# Power.net
KiCad netlist of a schematic drawn in Altium Designer
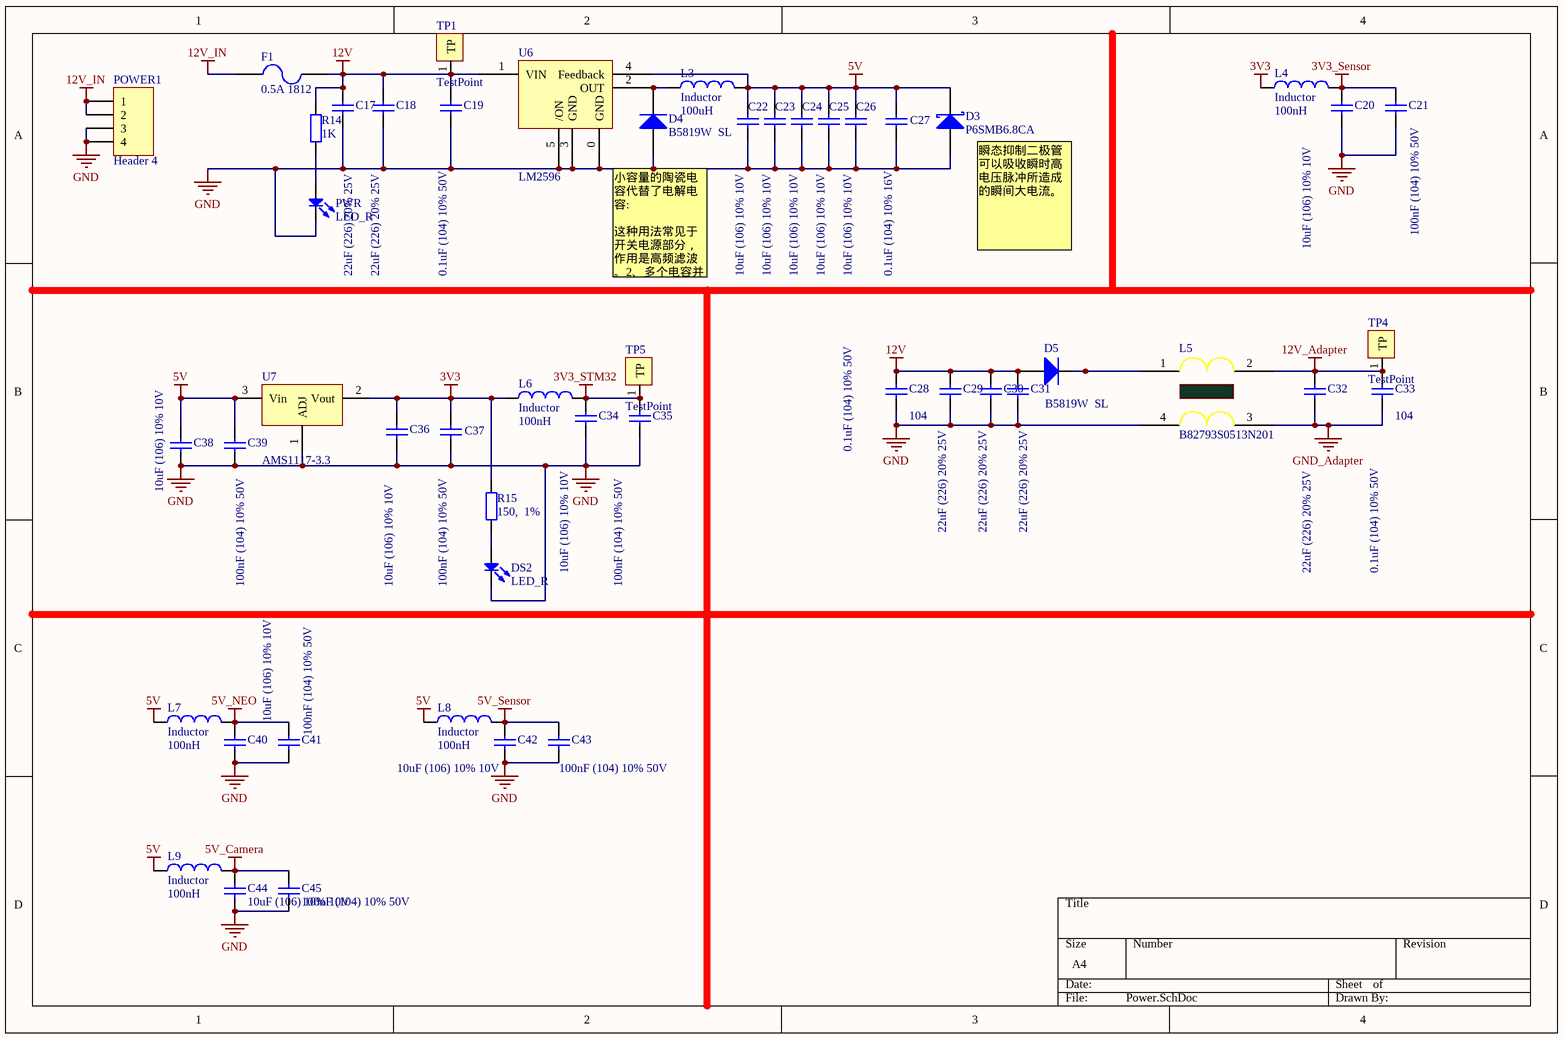
[diagram p0: Power.SchDoc]

(export (version "E")
  (design (tool "Eeschema 10.0.6"))
  (components
    (comp (ref "C17")
      (value "22uF (226) 20% 25V")
      (footprint "0805_C")
      (description "贴片电容")
      (libsource (lib "Miscellaneous Devices LC") (part "0805 22uF (226) 20% 25V"))
    )
    (comp (ref "C18")
      (value "22uF (226) 20% 25V")
      (footprint "0805_C")
      (description "贴片电容")
      (libsource (lib "Miscellaneous Devices LC") (part "0805 22uF (226) 20% 25V"))
    )
    (comp (ref "C19")
      (value "0.1uF (104) 10% 50V")
      (footprint "0805_C")
      (description "Capacitor")
      (fields (field (name "PUBLISHER") "Altium Limited"))
      (libsource (lib "Miscellaneous Devices") (part "Cap"))
    )
    (comp (ref "C20")
      (value "10uF (106) 10% 10V")
      (footprint "0603_C")
      (description "贴片电容")
      (libsource (lib "Miscellaneous Devices LC") (part "0603 10uF (106) 10% 10V"))
    )
    (comp (ref "C21")
      (value "100nF (104) 10% 50V")
      (footprint "0603_C")
      (description "贴片电容")
      (libsource (lib "Miscellaneous Devices LC") (part "0603 100nF (104) 10% 50V"))
    )
    (comp (ref "C22")
      (value "10uF (106) 10% 10V")
      (footprint "0603_C")
      (description "贴片电容")
      (libsource (lib "Miscellaneous Devices LC") (part "0603 10uF (106) 10% 10V"))
    )
    (comp (ref "C23")
      (value "10uF (106) 10% 10V")
      (footprint "0603_C")
      (description "贴片电容")
      (libsource (lib "Miscellaneous Devices LC") (part "0603 10uF (106) 10% 10V"))
    )
    (comp (ref "C24")
      (value "10uF (106) 10% 10V")
      (footprint "0603_C")
      (description "贴片电容")
      (libsource (lib "Miscellaneous Devices LC") (part "0603 10uF (106) 10% 10V"))
    )
    (comp (ref "C25")
      (value "10uF (106) 10% 10V")
      (footprint "0603_C")
      (description "贴片电容")
      (libsource (lib "Miscellaneous Devices LC") (part "0603 10uF (106) 10% 10V"))
    )
    (comp (ref "C26")
      (value "10uF (106) 10% 10V")
      (footprint "0603_C")
      (description "贴片电容")
      (libsource (lib "Miscellaneous Devices LC") (part "0603 10uF (106) 10% 10V"))
    )
    (comp (ref "C27")
      (value "0.1uF (104) 10% 16V")
      (footprint "0603_C")
      (description "Capacitor")
      (fields (field (name "PUBLISHER") "Altium Limited"))
      (libsource (lib "Miscellaneous Devices") (part "Cap"))
    )
    (comp (ref "C28")
      (value "0.1uF (104) 10% 50V")
      (footprint "0805_C")
      (description "Capacitor")
      (fields (field (name "ALTIUM_VALUE") "104") (field (name "PUBLISHER") "Altium Limited"))
      (libsource (lib "Miscellaneous Devices") (part "Cap"))
    )
    (comp (ref "C29")
      (value "22uF (226) 20% 25V")
      (footprint "0805_C")
      (description "贴片电容")
      (libsource (lib "Miscellaneous Devices LC") (part "0805 22uF (226) 20% 25V"))
    )
    (comp (ref "C30")
      (value "22uF (226) 20% 25V")
      (footprint "0805_C")
      (description "贴片电容")
      (libsource (lib "Miscellaneous Devices LC") (part "0805 22uF (226) 20% 25V"))
    )
    (comp (ref "C31")
      (value "22uF (226) 20% 25V")
      (footprint "0805_C")
      (description "贴片电容")
      (libsource (lib "Miscellaneous Devices LC") (part "0805 22uF (226) 20% 25V"))
    )
    (comp (ref "C32")
      (value "22uF (226) 20% 25V")
      (footprint "0805_C")
      (description "贴片电容")
      (libsource (lib "Miscellaneous Devices LC") (part "0805 22uF (226) 20% 25V"))
    )
    (comp (ref "C33")
      (value "0.1uF (104) 10% 50V")
      (footprint "0805_C")
      (description "Capacitor")
      (fields (field (name "ALTIUM_VALUE") "104") (field (name "PUBLISHER") "Altium Limited"))
      (libsource (lib "Miscellaneous Devices") (part "Cap"))
    )
    (comp (ref "C34")
      (value "10uF (106) 10% 10V")
      (footprint "0603_C")
      (description "贴片电容")
      (libsource (lib "Miscellaneous Devices LC") (part "0603 10uF (106) 10% 10V"))
    )
    (comp (ref "C35")
      (value "100nF (104) 10% 50V")
      (footprint "0603_C")
      (description "贴片电容")
      (libsource (lib "Miscellaneous Devices LC") (part "0603 100nF (104) 10% 50V"))
    )
    (comp (ref "C36")
      (value "10uF (106) 10% 10V")
      (footprint "0603_C")
      (description "贴片电容")
      (libsource (lib "Miscellaneous Devices LC") (part "0603 10uF (106) 10% 10V"))
    )
    (comp (ref "C37")
      (value "100nF (104) 10% 50V")
      (footprint "0603_C")
      (description "贴片电容")
      (libsource (lib "Miscellaneous Devices LC") (part "0603 100nF (104) 10% 50V"))
    )
    (comp (ref "C38")
      (value "10uF (106) 10% 10V")
      (footprint "0603_C")
      (description "贴片电容")
      (libsource (lib "Miscellaneous Devices LC") (part "0603 10uF (106) 10% 10V"))
    )
    (comp (ref "C39")
      (value "100nF (104) 10% 50V")
      (footprint "0603_C")
      (description "贴片电容")
      (libsource (lib "Miscellaneous Devices LC") (part "0603 100nF (104) 10% 50V"))
    )
    (comp (ref "C40")
      (value "10uF (106) 10% 10V")
      (footprint "0603_C")
      (description "贴片电容")
      (libsource (lib "Miscellaneous Devices LC") (part "0603 10uF (106) 10% 10V"))
    )
    (comp (ref "C41")
      (value "100nF (104) 10% 50V")
      (footprint "0603_C")
      (description "贴片电容")
      (libsource (lib "Miscellaneous Devices LC") (part "0603 100nF (104) 10% 50V"))
    )
    (comp (ref "C42")
      (value "10uF (106) 10% 10V")
      (footprint "0603_C")
      (description "贴片电容")
      (libsource (lib "Miscellaneous Devices LC") (part "0603 10uF (106) 10% 10V"))
    )
    (comp (ref "C43")
      (value "100nF (104) 10% 50V")
      (footprint "0603_C")
      (description "贴片电容")
      (libsource (lib "Miscellaneous Devices LC") (part "0603 100nF (104) 10% 50V"))
    )
    (comp (ref "C44")
      (value "10uF (106) 10% 10V")
      (footprint "0603_C")
      (description "贴片电容")
      (libsource (lib "Miscellaneous Devices LC") (part "0603 10uF (106) 10% 10V"))
    )
    (comp (ref "C45")
      (value "100nF (104) 10% 50V")
      (footprint "0603_C")
      (description "贴片电容")
      (libsource (lib "Miscellaneous Devices LC") (part "0603 100nF (104) 10% 50V"))
    )
    (comp (ref "D3")
      (value "P6SMB6.8CA")
      (footprint "SMB(DO-214AA)_S1")
      (description "Schottky Diode")
      (fields (field (name "PUBLISHER") "Altium Limited"))
      (libsource (lib "Miscellaneous Devices") (part "D Schottky"))
    )
    (comp (ref "D4")
      (value "B5819W  SL")
      (footprint "SOD-123")
      (description "肖特基二极管")
      (libsource (lib "Miscellaneous Devices LC") (part "SOD-123 B5819W  SL"))
    )
    (comp (ref "D5")
      (value "B5819W  SL")
      (footprint "SOD-123")
      (description "肖特基二极管")
      (libsource (lib "Miscellaneous Devices LC") (part "SOD-123 B5819W  SL"))
    )
    (comp (ref "DS2")
      (value "LED_R")
      (footprint "LED0603")
      (description "Typical RED, GREEN, YELLOW, AMBER GaAs LED")
      (fields (field (name "PUBLISHER") "Altium Limited"))
      (libsource (lib "Devices") (part "LED"))
    )
    (comp (ref "F1")
      (value "0.5A 1812")
      (footprint "1812")
      (description "Fuse")
      (fields (field (name "PUBLISHER") "Altium Limited"))
      (libsource (lib "Miscellaneous Devices") (part "Fuse 2"))
    )
    (comp (ref "L3")
      (value "Inductor")
      (footprint "L1050(10x10x4)")
      (fields (field (name "ALTIUM_VALUE") "100uH") (field (name "PUBLISHER") "Altium Limited"))
      (libsource (lib "Miscellaneous Devices") (part "Inductor"))
    )
    (comp (ref "L4")
      (value "Inductor")
      (footprint "0603_L")
      (fields (field (name "ALTIUM_VALUE") "100nH") (field (name "PUBLISHER") "Altium Limited"))
      (libsource (lib "Miscellaneous Devices") (part "Inductor"))
    )
    (comp (ref "L5")
      (value "B82793S0513N201")
      (footprint "B82793S0513N201_Yes")
      (libsource (lib "滤波器") (part "B82793S0513N201"))
    )
    (comp (ref "L6")
      (value "Inductor")
      (footprint "0603_L")
      (fields (field (name "ALTIUM_VALUE") "100nH") (field (name "PUBLISHER") "Altium Limited"))
      (libsource (lib "Miscellaneous Devices") (part "Inductor"))
    )
    (comp (ref "L7")
      (value "Inductor")
      (footprint "0603_L")
      (fields (field (name "ALTIUM_VALUE") "100nH") (field (name "PUBLISHER") "Altium Limited"))
      (libsource (lib "Miscellaneous Devices") (part "Inductor"))
    )
    (comp (ref "L8")
      (value "Inductor")
      (footprint "0603_L")
      (fields (field (name "ALTIUM_VALUE") "100nH") (field (name "PUBLISHER") "Altium Limited"))
      (libsource (lib "Miscellaneous Devices") (part "Inductor"))
    )
    (comp (ref "L9")
      (value "Inductor")
      (footprint "0603_L")
      (fields (field (name "ALTIUM_VALUE") "100nH") (field (name "PUBLISHER") "Altium Limited"))
      (libsource (lib "Miscellaneous Devices") (part "Inductor"))
    )
    (comp (ref "POWER1")
      (value "Header 4")
      (footprint "XH2.54_4P")
      (description "Header, 4-Pin")
      (fields (field (name "PUBLISHER") "Altium Limited"))
      (libsource (lib "Miscellaneous Connectors") (part "Header 4"))
    )
    (comp (ref "PWR")
      (value "LED_R")
      (footprint "LED0603")
      (description "Typical RED, GREEN, YELLOW, AMBER GaAs LED")
      (fields (field (name "PUBLISHER") "Altium Limited"))
      (libsource (lib "Devices") (part "LED"))
    )
    (comp (ref "R14")
      (value "1K")
      (footprint "R0603")
      (description "Resistor")
      (fields (field (name "PUBLISHER") "Altium Limited"))
      (libsource (lib "STM32F103C8T6(原理图库)") (part "Res2"))
    )
    (comp (ref "R15")
      (value "150,  1%")
      (footprint "R0603")
      (description "Resistor")
      (fields (field (name "PUBLISHER") "Altium Limited"))
      (libsource (lib "STM32F103C8T6(原理图库)") (part "Res2"))
    )
    (comp (ref "TP1") (value "TestPoint") (footprint "TP") (libsource (lib "my lib1") (part "TP")))
    (comp (ref "TP4") (value "TestPoint") (footprint "TP") (libsource (lib "my lib1") (part "TP")))
    (comp (ref "TP5") (value "TestPoint") (footprint "TP") (libsource (lib "my lib1") (part "TP")))
    (comp (ref "U6") (value "LM2596") (libsource (lib "STM32F103C8T6(原理图库)") (part "LM2576")))
    (comp (ref "U7")
      (value "AMS1117-3.3")
      (footprint "SOT-223")
      (description "3-Terminal Adjustable Positive Voltage Regulator")
      (libsource (lib "稳压器件") (part "LM317"))
    )
  )
  (nets
    (net (code "1") (name "3V3") (class "Default")
      (node (ref "C36") (pin "2") (pinfunction "2_2") (pintype "passive"))
      (node (ref "C37") (pin "2") (pinfunction "2_2") (pintype "passive"))
      (node (ref "L4") (pin "1") (pinfunction "1_1") (pintype "passive"))
      (node (ref "L6") (pin "1") (pinfunction "1_1") (pintype "passive"))
      (node (ref "R15") (pin "1") (pinfunction "1_1") (pintype "passive"))
      (node (ref "U7") (pin "2") (pinfunction "Vout_2") (pintype "passive"))
    )
    (net (code "2") (name "3V3_STM32") (class "Default")
      (node (ref "C34") (pin "2") (pinfunction "2_2") (pintype "passive"))
      (node (ref "C35") (pin "2") (pinfunction "2_2") (pintype "passive"))
      (node (ref "L6") (pin "2") (pinfunction "2_2") (pintype "passive"))
      (node (ref "TP5") (pin "1") (pinfunction "TP_1") (pintype "passive"))
    )
    (net (code "3") (name "3V3_Sensor") (class "Default")
      (node (ref "C20") (pin "2") (pinfunction "2_2") (pintype "passive"))
      (node (ref "C21") (pin "2") (pinfunction "2_2") (pintype "passive"))
      (node (ref "L4") (pin "2") (pinfunction "2_2") (pintype "passive"))
    )
    (net (code "4") (name "5V") (class "Default")
      (node (ref "C22") (pin "2") (pinfunction "2_2") (pintype "passive"))
      (node (ref "C23") (pin "2") (pinfunction "2_2") (pintype "passive"))
      (node (ref "C24") (pin "2") (pinfunction "2_2") (pintype "passive"))
      (node (ref "C25") (pin "2") (pinfunction "2_2") (pintype "passive"))
      (node (ref "C26") (pin "2") (pinfunction "2_2") (pintype "passive"))
      (node (ref "C27") (pin "2") (pinfunction "2_2") (pintype "passive"))
      (node (ref "C38") (pin "2") (pinfunction "2_2") (pintype "passive"))
      (node (ref "C39") (pin "2") (pinfunction "2_2") (pintype "passive"))
      (node (ref "D3") (pin "2") (pinfunction "K_2") (pintype "passive"))
      (node (ref "L3") (pin "2") (pinfunction "2_2") (pintype "passive"))
      (node (ref "L7") (pin "1") (pinfunction "1_1") (pintype "passive"))
      (node (ref "L8") (pin "1") (pinfunction "1_1") (pintype "passive"))
      (node (ref "L9") (pin "1") (pinfunction "1_1") (pintype "passive"))
      (node (ref "U6") (pin "4") (pinfunction "Feedback_4") (pintype "passive"))
      (node (ref "U7") (pin "3") (pinfunction "Vin_3") (pintype "passive"))
    )
    (net (code "5") (name "5V_Camera") (class "Default")
      (node (ref "C44") (pin "2") (pinfunction "2_2") (pintype "passive"))
      (node (ref "C45") (pin "2") (pinfunction "2_2") (pintype "passive"))
      (node (ref "L9") (pin "2") (pinfunction "2_2") (pintype "passive"))
    )
    (net (code "6") (name "5V_NEO") (class "Default")
      (node (ref "C40") (pin "2") (pinfunction "2_2") (pintype "passive"))
      (node (ref "C41") (pin "2") (pinfunction "2_2") (pintype "passive"))
      (node (ref "L7") (pin "2") (pinfunction "2_2") (pintype "passive"))
    )
    (net (code "7") (name "5V_Sensor") (class "Default")
      (node (ref "C42") (pin "2") (pinfunction "2_2") (pintype "passive"))
      (node (ref "C43") (pin "2") (pinfunction "2_2") (pintype "passive"))
      (node (ref "L8") (pin "2") (pinfunction "2_2") (pintype "passive"))
    )
    (net (code "8") (name "12V") (class "Default")
      (node (ref "C17") (pin "2") (pinfunction "2_2") (pintype "passive"))
      (node (ref "C18") (pin "2") (pinfunction "2_2") (pintype "passive"))
      (node (ref "C19") (pin "2") (pinfunction "2_2") (pintype "passive"))
      (node (ref "C28") (pin "2") (pinfunction "2_2") (pintype "passive"))
      (node (ref "C29") (pin "2") (pinfunction "2_2") (pintype "passive"))
      (node (ref "C30") (pin "2") (pinfunction "2_2") (pintype "passive"))
      (node (ref "C31") (pin "2") (pinfunction "2_2") (pintype "passive"))
      (node (ref "D5") (pin "1") (pinfunction "A_1") (pintype "passive"))
      (node (ref "F1") (pin "2") (pinfunction "2_2") (pintype "passive"))
      (node (ref "R14") (pin "1") (pinfunction "1_1") (pintype "passive"))
      (node (ref "TP1") (pin "1") (pinfunction "TP_1") (pintype "passive"))
      (node (ref "U6") (pin "1") (pinfunction "VIN_1") (pintype "passive"))
    )
    (net (code "9") (name "12V_Adapter") (class "Default")
      (node (ref "C32") (pin "2") (pinfunction "2_2") (pintype "passive"))
      (node (ref "C33") (pin "2") (pinfunction "2_2") (pintype "passive"))
      (node (ref "L5") (pin "2") (pinfunction "2_2") (pintype "passive"))
      (node (ref "TP4") (pin "1") (pinfunction "TP_1") (pintype "passive"))
    )
    (net (code "10") (name "12V_IN") (class "Default")
      (node (ref "F1") (pin "1") (pinfunction "1_1") (pintype "passive"))
      (node (ref "POWER1") (pin "1") (pinfunction "1_1") (pintype "passive"))
      (node (ref "POWER1") (pin "2") (pinfunction "2_2") (pintype "passive"))
    )
    (net (code "11") (name "GND") (class "Default")
      (node (ref "C17") (pin "1") (pinfunction "1_1") (pintype "passive"))
      (node (ref "C18") (pin "1") (pinfunction "1_1") (pintype "passive"))
      (node (ref "C19") (pin "1") (pinfunction "1_1") (pintype "passive"))
      (node (ref "C20") (pin "1") (pinfunction "1_1") (pintype "passive"))
      (node (ref "C21") (pin "1") (pinfunction "1_1") (pintype "passive"))
      (node (ref "C22") (pin "1") (pinfunction "1_1") (pintype "passive"))
      (node (ref "C23") (pin "1") (pinfunction "1_1") (pintype "passive"))
      (node (ref "C24") (pin "1") (pinfunction "1_1") (pintype "passive"))
      (node (ref "C25") (pin "1") (pinfunction "1_1") (pintype "passive"))
      (node (ref "C26") (pin "1") (pinfunction "1_1") (pintype "passive"))
      (node (ref "C27") (pin "1") (pinfunction "1_1") (pintype "passive"))
      (node (ref "C28") (pin "1") (pinfunction "1_1") (pintype "passive"))
      (node (ref "C29") (pin "1") (pinfunction "1_1") (pintype "passive"))
      (node (ref "C30") (pin "1") (pinfunction "1_1") (pintype "passive"))
      (node (ref "C31") (pin "1") (pinfunction "1_1") (pintype "passive"))
      (node (ref "C34") (pin "1") (pinfunction "1_1") (pintype "passive"))
      (node (ref "C35") (pin "1") (pinfunction "1_1") (pintype "passive"))
      (node (ref "C36") (pin "1") (pinfunction "1_1") (pintype "passive"))
      (node (ref "C37") (pin "1") (pinfunction "1_1") (pintype "passive"))
      (node (ref "C38") (pin "1") (pinfunction "1_1") (pintype "passive"))
      (node (ref "C39") (pin "1") (pinfunction "1_1") (pintype "passive"))
      (node (ref "C40") (pin "1") (pinfunction "1_1") (pintype "passive"))
      (node (ref "C41") (pin "1") (pinfunction "1_1") (pintype "passive"))
      (node (ref "C42") (pin "1") (pinfunction "1_1") (pintype "passive"))
      (node (ref "C43") (pin "1") (pinfunction "1_1") (pintype "passive"))
      (node (ref "C44") (pin "1") (pinfunction "1_1") (pintype "passive"))
      (node (ref "C45") (pin "1") (pinfunction "1_1") (pintype "passive"))
      (node (ref "D3") (pin "1") (pinfunction "A_1") (pintype "passive"))
      (node (ref "D4") (pin "1") (pinfunction "A_1") (pintype "passive"))
      (node (ref "DS2") (pin "2") (pinfunction "K_2") (pintype "passive"))
      (node (ref "L5") (pin "4") (pinfunction "4_4") (pintype "passive"))
      (node (ref "POWER1") (pin "3") (pinfunction "3_3") (pintype "passive"))
      (node (ref "POWER1") (pin "4") (pinfunction "4_4") (pintype "passive"))
      (node (ref "PWR") (pin "2") (pinfunction "K_2") (pintype "passive"))
      (node (ref "U6") (pin "0") (pinfunction "GND_0") (pintype "passive"))
      (node (ref "U6") (pin "3") (pinfunction "GND_3") (pintype "passive"))
      (node (ref "U6") (pin "5") (pinfunction "/ON_5") (pintype "passive"))
      (node (ref "U7") (pin "1") (pinfunction "ADJ_1") (pintype "passive"))
    )
    (net (code "12") (name "GND_Adapter") (class "Default")
      (node (ref "C32") (pin "1") (pinfunction "1_1") (pintype "passive"))
      (node (ref "C33") (pin "1") (pinfunction "1_1") (pintype "passive"))
      (node (ref "L5") (pin "3") (pinfunction "3_3") (pintype "passive"))
    )
    (net (code "13") (name "Net-(D4-K)") (class "Default")
      (node (ref "D4") (pin "2") (pinfunction "K_2") (pintype "passive"))
      (node (ref "L3") (pin "1") (pinfunction "1_1") (pintype "passive"))
      (node (ref "U6") (pin "2") (pinfunction "OUT_2") (pintype "passive"))
    )
    (net (code "14") (name "Net-(D5-K)") (class "Default")
      (node (ref "D5") (pin "2") (pinfunction "K_2") (pintype "passive"))
      (node (ref "L5") (pin "1") (pinfunction "1_1") (pintype "passive"))
    )
    (net (code "15") (name "Net-(DS2-A)") (class "Default")
      (node (ref "DS2") (pin "1") (pinfunction "A_1") (pintype "passive"))
      (node (ref "R15") (pin "2") (pinfunction "2_2") (pintype "passive"))
    )
    (net (code "16") (name "Net-(PWR-A)") (class "Default")
      (node (ref "PWR") (pin "1") (pinfunction "A_1") (pintype "passive"))
      (node (ref "R14") (pin "2") (pinfunction "2_2") (pintype "passive"))
    )
  )
)
